# hub.net
KiCad netlist of a schematic drawn in EAGLE
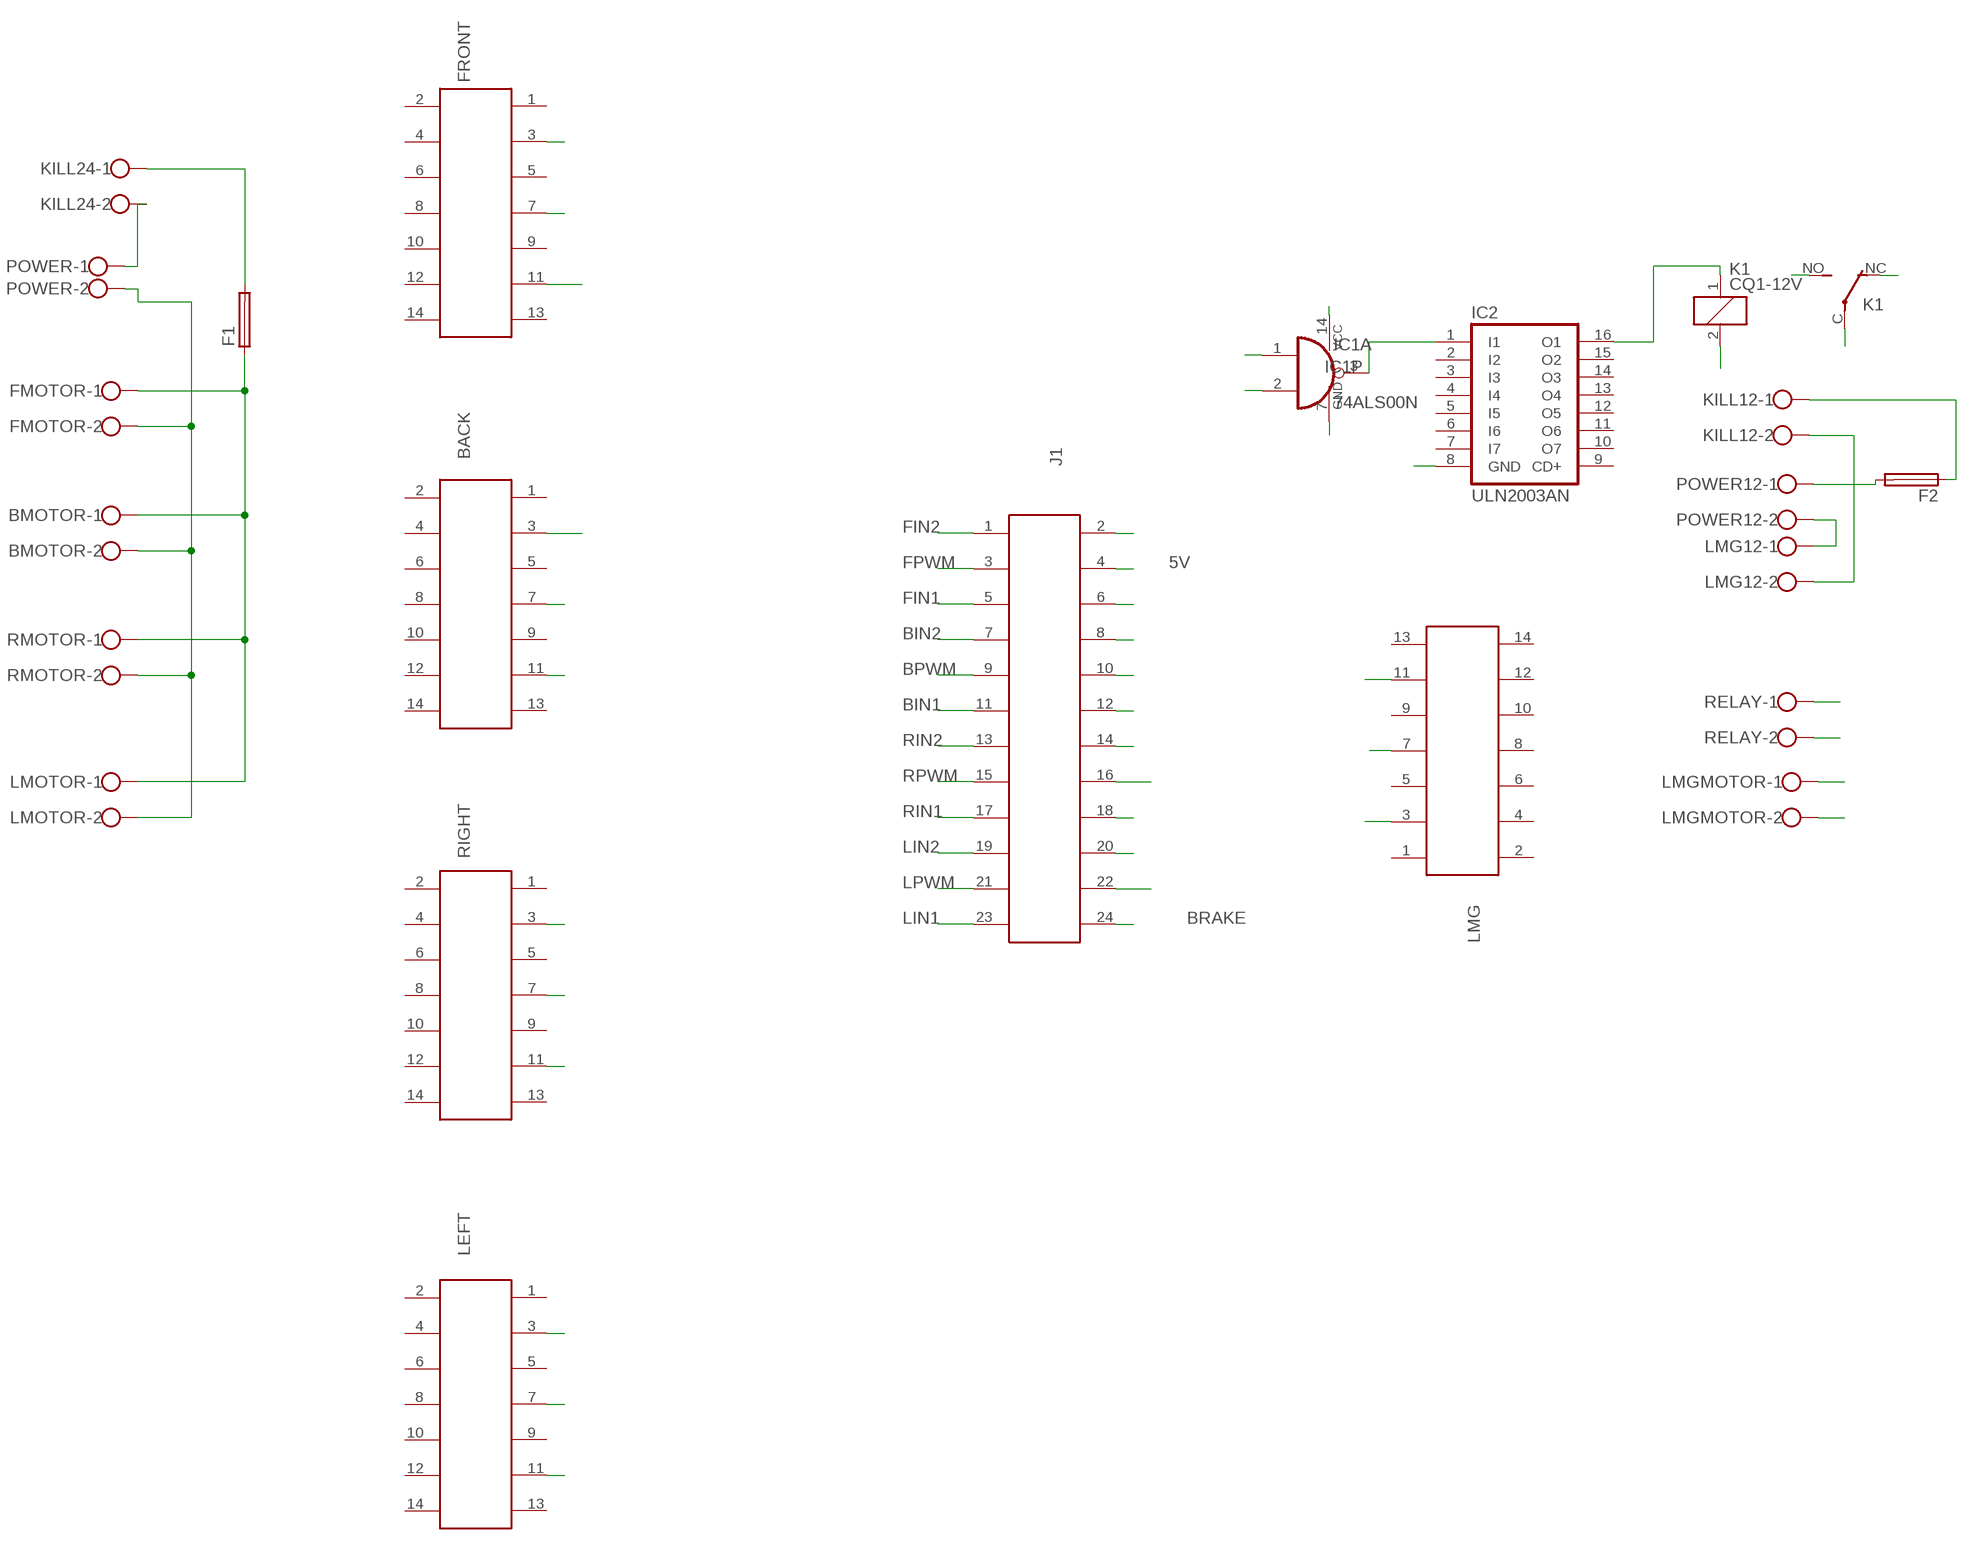
[diagram p0: schematic, sheet 1]

(export (version "E")
  (design (tool "Eeschema 10.0.6"))
  (components
    (comp (ref "BACK")
      (value "612014235121")
      (footprint "eagle-import:612014235121")
      (libsource (lib "eagle-import") (part "612014235121"))
    )
    (comp (ref "BMOTOR")
      (value "W237-102")
      (footprint "eagle-import:W237-102")
      (fields (field (name "MPN") "237-102"))
      (libsource (lib "eagle-import") (part "W237-102"))
    )
    (comp (ref "F1")
      (value "GSH15")
      (footprint "eagle-import:GSH15")
      (fields (field (name "MPN") "64900001039"))
      (libsource (lib "eagle-import") (part "GSH15"))
    )
    (comp (ref "F2")
      (value "GSH15")
      (footprint "eagle-import:GSH15")
      (fields (field (name "MPN") "64900001039"))
      (libsource (lib "eagle-import") (part "GSH15"))
    )
    (comp (ref "FMOTOR")
      (value "W237-102")
      (footprint "eagle-import:W237-102")
      (fields (field (name "MPN") "237-102"))
      (libsource (lib "eagle-import") (part "W237-102"))
    )
    (comp (ref "FRONT")
      (value "612014235121")
      (footprint "eagle-import:612014235121")
      (libsource (lib "eagle-import") (part "612014235121"))
    )
    (comp (ref "IC1")
      (value "74ALS00N")
      (footprint "eagle-import:DIL14")
      (libsource (lib "eagle-import") (part "7400NALS"))
    )
    (comp (ref "IC2")
      (value "ULN2003AN")
      (footprint "eagle-import:DIL16")
      (libsource (lib "eagle-import") (part "ULN2003AN"))
    )
    (comp (ref "J1")
      (value "61202421621")
      (footprint "eagle-import:61202421621")
      (libsource (lib "eagle-import") (part "61202421621"))
    )
    (comp (ref "K1")
      (value "CQ1-12V")
      (footprint "eagle-import:CQ1")
      (libsource (lib "eagle-import") (part "CQ1-12V"))
    )
    (comp (ref "KILL12")
      (value "W237-102")
      (footprint "eagle-import:W237-102")
      (fields (field (name "MPN") "237-102"))
      (libsource (lib "eagle-import") (part "W237-102"))
    )
    (comp (ref "KILL24")
      (value "W237-102")
      (footprint "eagle-import:W237-102")
      (fields (field (name "MPN") "237-102"))
      (libsource (lib "eagle-import") (part "W237-102"))
    )
    (comp (ref "LEFT")
      (value "612014235121")
      (footprint "eagle-import:612014235121")
      (libsource (lib "eagle-import") (part "612014235121"))
    )
    (comp (ref "LMG")
      (value "612014235121")
      (footprint "eagle-import:612014235121")
      (libsource (lib "eagle-import") (part "612014235121"))
    )
    (comp (ref "LMG12")
      (value "W237-102")
      (footprint "eagle-import:W237-102")
      (fields (field (name "MPN") "237-102"))
      (libsource (lib "eagle-import") (part "W237-102"))
    )
    (comp (ref "LMGMOTOR")
      (value "W237-102")
      (footprint "eagle-import:W237-102")
      (fields (field (name "MPN") "237-102"))
      (libsource (lib "eagle-import") (part "W237-102"))
    )
    (comp (ref "LMOTOR")
      (value "W237-102")
      (footprint "eagle-import:W237-102")
      (fields (field (name "MPN") "237-102"))
      (libsource (lib "eagle-import") (part "W237-102"))
    )
    (comp (ref "POWER")
      (value "W237-102")
      (footprint "eagle-import:W237-102")
      (fields (field (name "MPN") "237-102"))
      (libsource (lib "eagle-import") (part "W237-102"))
    )
    (comp (ref "POWER12")
      (value "W237-102")
      (footprint "eagle-import:W237-102")
      (fields (field (name "MPN") "237-102"))
      (libsource (lib "eagle-import") (part "W237-102"))
    )
    (comp (ref "RELAY")
      (value "W237-102")
      (footprint "eagle-import:W237-102")
      (fields (field (name "MPN") "237-102"))
      (libsource (lib "eagle-import") (part "W237-102"))
    )
    (comp (ref "RIGHT")
      (value "612014235121")
      (footprint "eagle-import:612014235121")
      (libsource (lib "eagle-import") (part "612014235121"))
    )
    (comp (ref "RMOTOR")
      (value "W237-102")
      (footprint "eagle-import:W237-102")
      (fields (field (name "MPN") "237-102"))
      (libsource (lib "eagle-import") (part "W237-102"))
    )
  )
  (nets
    (net (code "1") (name "/5V") (class "Default")
      (node (ref "IC1") (pin "1") (pinfunction "I0_1") (pintype "input"))
      (node (ref "IC1") (pin "14") (pinfunction "VCC_14") (pintype "power_in"))
      (node (ref "J1") (pin "4") (pinfunction "4_4") (pintype "passive"))
      (node (ref "K1") (pin "2") (pinfunction "2_2") (pintype "passive"))
    )
    (net (code "2") (name "/BIN1") (class "Default")
      (node (ref "BACK") (pin "3") (pinfunction "3_3") (pintype "passive"))
      (node (ref "J1") (pin "11") (pinfunction "11_11") (pintype "passive"))
    )
    (net (code "3") (name "/BIN2") (class "Default")
      (node (ref "BACK") (pin "11") (pinfunction "11_11") (pintype "passive"))
      (node (ref "J1") (pin "7") (pinfunction "7_7") (pintype "passive"))
    )
    (net (code "4") (name "/BPWM") (class "Default")
      (node (ref "BACK") (pin "7") (pinfunction "7_7") (pintype "passive"))
      (node (ref "J1") (pin "9") (pinfunction "9_9") (pintype "passive"))
    )
    (net (code "5") (name "/BRAKE") (class "Default")
      (node (ref "IC1") (pin "2") (pinfunction "I1_2") (pintype "input"))
      (node (ref "J1") (pin "24") (pinfunction "24_24") (pintype "passive"))
    )
    (net (code "6") (name "/COM") (class "Default")
      (node (ref "K1") (pin "C") (pinfunction "P_C") (pintype "passive"))
      (node (ref "LMGMOTOR") (pin "2") (pinfunction "KL_2") (pintype "passive"))
      (node (ref "RELAY") (pin "2") (pinfunction "KL_2") (pintype "passive"))
    )
    (net (code "7") (name "/FIN1") (class "Default")
      (node (ref "FRONT") (pin "3") (pinfunction "3_3") (pintype "passive"))
      (node (ref "J1") (pin "5") (pinfunction "5_5") (pintype "passive"))
    )
    (net (code "8") (name "/FIN2") (class "Default")
      (node (ref "FRONT") (pin "11") (pinfunction "11_11") (pintype "passive"))
      (node (ref "J1") (pin "1") (pinfunction "1_1") (pintype "passive"))
    )
    (net (code "9") (name "/FPWM") (class "Default")
      (node (ref "FRONT") (pin "7") (pinfunction "7_7") (pintype "passive"))
      (node (ref "J1") (pin "3") (pinfunction "3_3") (pintype "passive"))
    )
    (net (code "10") (name "/GND") (class "Default")
      (node (ref "BMOTOR") (pin "2") (pinfunction "KL_2") (pintype "passive"))
      (node (ref "FMOTOR") (pin "2") (pinfunction "KL_2") (pintype "passive"))
      (node (ref "IC1") (pin "7") (pinfunction "GND_7") (pintype "power_in"))
      (node (ref "IC2") (pin "8") (pinfunction "GND_8") (pintype "power_in"))
      (node (ref "LMOTOR") (pin "2") (pinfunction "KL_2") (pintype "passive"))
      (node (ref "POWER") (pin "2") (pinfunction "KL_2") (pintype "passive"))
      (node (ref "RMOTOR") (pin "2") (pinfunction "KL_2") (pintype "passive"))
    )
    (net (code "11") (name "/LIN1") (class "Default")
      (node (ref "J1") (pin "23") (pinfunction "23_23") (pintype "passive"))
      (node (ref "LEFT") (pin "3") (pinfunction "3_3") (pintype "passive"))
    )
    (net (code "12") (name "/LIN2") (class "Default")
      (node (ref "J1") (pin "19") (pinfunction "19_19") (pintype "passive"))
      (node (ref "LEFT") (pin "11") (pinfunction "11_11") (pintype "passive"))
    )
    (net (code "13") (name "/LMG1") (class "Default")
      (node (ref "J1") (pin "14") (pinfunction "14_14") (pintype "passive"))
      (node (ref "LMG") (pin "3") (pinfunction "3_3") (pintype "passive"))
    )
    (net (code "14") (name "/LMG2") (class "Default")
      (node (ref "J1") (pin "18") (pinfunction "18_18") (pintype "passive"))
      (node (ref "LMG") (pin "11") (pinfunction "11_11") (pintype "passive"))
    )
    (net (code "15") (name "/LMGPWM") (class "Default")
      (node (ref "J1") (pin "16") (pinfunction "16_16") (pintype "passive"))
      (node (ref "LMG") (pin "7") (pinfunction "7_7") (pintype "passive"))
    )
    (net (code "16") (name "/LPWM") (class "Default")
      (node (ref "J1") (pin "21") (pinfunction "21_21") (pintype "passive"))
      (node (ref "LEFT") (pin "7") (pinfunction "7_7") (pintype "passive"))
    )
    (net (code "17") (name "/NO") (class "Default")
      (node (ref "K1") (pin "NO") (pinfunction "S_NO") (pintype "passive"))
      (node (ref "LMGMOTOR") (pin "1") (pinfunction "KL_1") (pintype "passive"))
      (node (ref "RELAY") (pin "1") (pinfunction "KL_1") (pintype "passive"))
    )
    (net (code "18") (name "/RIN1") (class "Default")
      (node (ref "J1") (pin "17") (pinfunction "17_17") (pintype "passive"))
      (node (ref "RIGHT") (pin "3") (pinfunction "3_3") (pintype "passive"))
    )
    (net (code "19") (name "/RIN2") (class "Default")
      (node (ref "J1") (pin "13") (pinfunction "13_13") (pintype "passive"))
      (node (ref "RIGHT") (pin "11") (pinfunction "11_11") (pintype "passive"))
    )
    (net (code "20") (name "/RPWM") (class "Default")
      (node (ref "J1") (pin "15") (pinfunction "15_15") (pintype "passive"))
      (node (ref "RIGHT") (pin "7") (pinfunction "7_7") (pintype "passive"))
    )
    (net (code "21") (name "Net-(BMOTORA-KL)") (class "Default")
      (node (ref "BMOTOR") (pin "1") (pinfunction "KL_1") (pintype "passive"))
      (node (ref "F1") (pin "1") (pinfunction "1_1") (pintype "passive"))
      (node (ref "FMOTOR") (pin "1") (pinfunction "KL_1") (pintype "passive"))
      (node (ref "LMOTOR") (pin "1") (pinfunction "KL_1") (pintype "passive"))
      (node (ref "RMOTOR") (pin "1") (pinfunction "KL_1") (pintype "passive"))
    )
    (net (code "22") (name "Net-(IC1A-O)") (class "Default")
      (node (ref "IC1") (pin "3") (pinfunction "O_3") (pintype "output"))
      (node (ref "IC2") (pin "1") (pinfunction "I1_1") (pintype "input"))
    )
    (net (code "23") (name "Net-(IC2-O1)") (class "Default")
      (node (ref "IC2") (pin "16") (pinfunction "O1_16") (pintype "open_collector"))
      (node (ref "K1") (pin "1") (pinfunction "1_1") (pintype "passive"))
    )
    (net (code "24") (name "Net-(KILL12A-KL)") (class "Default")
      (node (ref "F2") (pin "1") (pinfunction "1_1") (pintype "passive"))
      (node (ref "KILL12") (pin "1") (pinfunction "KL_1") (pintype "passive"))
    )
    (net (code "25") (name "Net-(KILL12B-KL)") (class "Default")
      (node (ref "KILL12") (pin "2") (pinfunction "KL_2") (pintype "passive"))
      (node (ref "LMG12") (pin "2") (pinfunction "KL_2") (pintype "passive"))
    )
    (net (code "26") (name "Net-(KILL24A-KL)") (class "Default")
      (node (ref "F1") (pin "2") (pinfunction "2_2") (pintype "passive"))
      (node (ref "KILL24") (pin "1") (pinfunction "KL_1") (pintype "passive"))
    )
    (net (code "27") (name "Net-(KILL24B-KL)") (class "Default")
      (node (ref "KILL24") (pin "2") (pinfunction "KL_2") (pintype "passive"))
      (node (ref "POWER") (pin "1") (pinfunction "KL_1") (pintype "passive"))
    )
    (net (code "28") (name "Net-(LMG12A-KL)") (class "Default")
      (node (ref "LMG12") (pin "1") (pinfunction "KL_1") (pintype "passive"))
      (node (ref "POWER12") (pin "2") (pinfunction "KL_2") (pintype "passive"))
    )
    (net (code "29") (name "Net-(POWER12A-KL)") (class "Default")
      (node (ref "F2") (pin "2") (pinfunction "2_2") (pintype "passive"))
      (node (ref "POWER12") (pin "1") (pinfunction "KL_1") (pintype "passive"))
    )
    (net (code "30") (name "unconnected-(BACK-Pad1)") (class "Default")
      (node (ref "BACK") (pin "1") (pinfunction "1_1") (pintype "passive"))
    )
    (net (code "31") (name "unconnected-(BACK-Pad2)") (class "Default")
      (node (ref "BACK") (pin "2") (pinfunction "2_2") (pintype "passive"))
    )
    (net (code "32") (name "unconnected-(BACK-Pad4)") (class "Default")
      (node (ref "BACK") (pin "4") (pinfunction "4_4") (pintype "passive"))
    )
    (net (code "33") (name "unconnected-(BACK-Pad5)") (class "Default")
      (node (ref "BACK") (pin "5") (pinfunction "5_5") (pintype "passive"))
    )
    (net (code "34") (name "unconnected-(BACK-Pad6)") (class "Default")
      (node (ref "BACK") (pin "6") (pinfunction "6_6") (pintype "passive"))
    )
    (net (code "35") (name "unconnected-(BACK-Pad8)") (class "Default")
      (node (ref "BACK") (pin "8") (pinfunction "8_8") (pintype "passive"))
    )
    (net (code "36") (name "unconnected-(BACK-Pad9)") (class "Default")
      (node (ref "BACK") (pin "9") (pinfunction "9_9") (pintype "passive"))
    )
    (net (code "37") (name "unconnected-(BACK-Pad10)") (class "Default")
      (node (ref "BACK") (pin "10") (pinfunction "10_10") (pintype "passive"))
    )
    (net (code "38") (name "unconnected-(BACK-Pad12)") (class "Default")
      (node (ref "BACK") (pin "12") (pinfunction "12_12") (pintype "passive"))
    )
    (net (code "39") (name "unconnected-(BACK-Pad13)") (class "Default")
      (node (ref "BACK") (pin "13") (pinfunction "13_13") (pintype "passive"))
    )
    (net (code "40") (name "unconnected-(BACK-Pad14)") (class "Default")
      (node (ref "BACK") (pin "14") (pinfunction "14_14") (pintype "passive"))
    )
    (net (code "41") (name "unconnected-(FRONT-Pad1)") (class "Default")
      (node (ref "FRONT") (pin "1") (pinfunction "1_1") (pintype "passive"))
    )
    (net (code "42") (name "unconnected-(FRONT-Pad2)") (class "Default")
      (node (ref "FRONT") (pin "2") (pinfunction "2_2") (pintype "passive"))
    )
    (net (code "43") (name "unconnected-(FRONT-Pad4)") (class "Default")
      (node (ref "FRONT") (pin "4") (pinfunction "4_4") (pintype "passive"))
    )
    (net (code "44") (name "unconnected-(FRONT-Pad5)") (class "Default")
      (node (ref "FRONT") (pin "5") (pinfunction "5_5") (pintype "passive"))
    )
    (net (code "45") (name "unconnected-(FRONT-Pad6)") (class "Default")
      (node (ref "FRONT") (pin "6") (pinfunction "6_6") (pintype "passive"))
    )
    (net (code "46") (name "unconnected-(FRONT-Pad8)") (class "Default")
      (node (ref "FRONT") (pin "8") (pinfunction "8_8") (pintype "passive"))
    )
    (net (code "47") (name "unconnected-(FRONT-Pad9)") (class "Default")
      (node (ref "FRONT") (pin "9") (pinfunction "9_9") (pintype "passive"))
    )
    (net (code "48") (name "unconnected-(FRONT-Pad10)") (class "Default")
      (node (ref "FRONT") (pin "10") (pinfunction "10_10") (pintype "passive"))
    )
    (net (code "49") (name "unconnected-(FRONT-Pad12)") (class "Default")
      (node (ref "FRONT") (pin "12") (pinfunction "12_12") (pintype "passive"))
    )
    (net (code "50") (name "unconnected-(FRONT-Pad13)") (class "Default")
      (node (ref "FRONT") (pin "13") (pinfunction "13_13") (pintype "passive"))
    )
    (net (code "51") (name "unconnected-(FRONT-Pad14)") (class "Default")
      (node (ref "FRONT") (pin "14") (pinfunction "14_14") (pintype "passive"))
    )
    (net (code "52") (name "unconnected-(IC2-CD+-Pad9)") (class "Default")
      (node (ref "IC2") (pin "9") (pinfunction "CD+_9") (pintype "passive"))
    )
    (net (code "53") (name "unconnected-(IC2-I2-Pad2)") (class "Default")
      (node (ref "IC2") (pin "2") (pinfunction "I2_2") (pintype "input"))
    )
    (net (code "54") (name "unconnected-(IC2-I3-Pad3)") (class "Default")
      (node (ref "IC2") (pin "3") (pinfunction "I3_3") (pintype "input"))
    )
    (net (code "55") (name "unconnected-(IC2-I4-Pad4)") (class "Default")
      (node (ref "IC2") (pin "4") (pinfunction "I4_4") (pintype "input"))
    )
    (net (code "56") (name "unconnected-(IC2-I5-Pad5)") (class "Default")
      (node (ref "IC2") (pin "5") (pinfunction "I5_5") (pintype "input"))
    )
    (net (code "57") (name "unconnected-(IC2-I6-Pad6)") (class "Default")
      (node (ref "IC2") (pin "6") (pinfunction "I6_6") (pintype "input"))
    )
    (net (code "58") (name "unconnected-(IC2-I7-Pad7)") (class "Default")
      (node (ref "IC2") (pin "7") (pinfunction "I7_7") (pintype "input"))
    )
    (net (code "59") (name "unconnected-(IC2-O2-Pad15)") (class "Default")
      (node (ref "IC2") (pin "15") (pinfunction "O2_15") (pintype "open_collector"))
    )
    (net (code "60") (name "unconnected-(IC2-O3-Pad14)") (class "Default")
      (node (ref "IC2") (pin "14") (pinfunction "O3_14") (pintype "open_collector"))
    )
    (net (code "61") (name "unconnected-(IC2-O4-Pad13)") (class "Default")
      (node (ref "IC2") (pin "13") (pinfunction "O4_13") (pintype "open_collector"))
    )
    (net (code "62") (name "unconnected-(IC2-O5-Pad12)") (class "Default")
      (node (ref "IC2") (pin "12") (pinfunction "O5_12") (pintype "open_collector"))
    )
    (net (code "63") (name "unconnected-(IC2-O6-Pad11)") (class "Default")
      (node (ref "IC2") (pin "11") (pinfunction "O6_11") (pintype "open_collector"))
    )
    (net (code "64") (name "unconnected-(IC2-O7-Pad10)") (class "Default")
      (node (ref "IC2") (pin "10") (pinfunction "O7_10") (pintype "open_collector"))
    )
    (net (code "65") (name "unconnected-(J1-Pad2)") (class "Default")
      (node (ref "J1") (pin "2") (pinfunction "2_2") (pintype "passive"))
    )
    (net (code "66") (name "unconnected-(J1-Pad6)") (class "Default")
      (node (ref "J1") (pin "6") (pinfunction "6_6") (pintype "passive"))
    )
    (net (code "67") (name "unconnected-(J1-Pad8)") (class "Default")
      (node (ref "J1") (pin "8") (pinfunction "8_8") (pintype "passive"))
    )
    (net (code "68") (name "unconnected-(J1-Pad10)") (class "Default")
      (node (ref "J1") (pin "10") (pinfunction "10_10") (pintype "passive"))
    )
    (net (code "69") (name "unconnected-(J1-Pad12)") (class "Default")
      (node (ref "J1") (pin "12") (pinfunction "12_12") (pintype "passive"))
    )
    (net (code "70") (name "unconnected-(J1-Pad20)") (class "Default")
      (node (ref "J1") (pin "20") (pinfunction "20_20") (pintype "passive"))
    )
    (net (code "71") (name "unconnected-(J1-Pad22)") (class "Default")
      (node (ref "J1") (pin "22") (pinfunction "22_22") (pintype "passive"))
    )
    (net (code "72") (name "unconnected-(K1B-O-PadNC)") (class "Default")
      (node (ref "K1") (pin "NC") (pinfunction "O_NC") (pintype "passive"))
    )
    (net (code "73") (name "unconnected-(LEFT-Pad1)") (class "Default")
      (node (ref "LEFT") (pin "1") (pinfunction "1_1") (pintype "passive"))
    )
    (net (code "74") (name "unconnected-(LEFT-Pad2)") (class "Default")
      (node (ref "LEFT") (pin "2") (pinfunction "2_2") (pintype "passive"))
    )
    (net (code "75") (name "unconnected-(LEFT-Pad4)") (class "Default")
      (node (ref "LEFT") (pin "4") (pinfunction "4_4") (pintype "passive"))
    )
    (net (code "76") (name "unconnected-(LEFT-Pad5)") (class "Default")
      (node (ref "LEFT") (pin "5") (pinfunction "5_5") (pintype "passive"))
    )
    (net (code "77") (name "unconnected-(LEFT-Pad6)") (class "Default")
      (node (ref "LEFT") (pin "6") (pinfunction "6_6") (pintype "passive"))
    )
    (net (code "78") (name "unconnected-(LEFT-Pad8)") (class "Default")
      (node (ref "LEFT") (pin "8") (pinfunction "8_8") (pintype "passive"))
    )
    (net (code "79") (name "unconnected-(LEFT-Pad9)") (class "Default")
      (node (ref "LEFT") (pin "9") (pinfunction "9_9") (pintype "passive"))
    )
    (net (code "80") (name "unconnected-(LEFT-Pad10)") (class "Default")
      (node (ref "LEFT") (pin "10") (pinfunction "10_10") (pintype "passive"))
    )
    (net (code "81") (name "unconnected-(LEFT-Pad12)") (class "Default")
      (node (ref "LEFT") (pin "12") (pinfunction "12_12") (pintype "passive"))
    )
    (net (code "82") (name "unconnected-(LEFT-Pad13)") (class "Default")
      (node (ref "LEFT") (pin "13") (pinfunction "13_13") (pintype "passive"))
    )
    (net (code "83") (name "unconnected-(LEFT-Pad14)") (class "Default")
      (node (ref "LEFT") (pin "14") (pinfunction "14_14") (pintype "passive"))
    )
    (net (code "84") (name "unconnected-(LMG-Pad1)") (class "Default")
      (node (ref "LMG") (pin "1") (pinfunction "1_1") (pintype "passive"))
    )
    (net (code "85") (name "unconnected-(LMG-Pad2)") (class "Default")
      (node (ref "LMG") (pin "2") (pinfunction "2_2") (pintype "passive"))
    )
    (net (code "86") (name "unconnected-(LMG-Pad4)") (class "Default")
      (node (ref "LMG") (pin "4") (pinfunction "4_4") (pintype "passive"))
    )
    (net (code "87") (name "unconnected-(LMG-Pad5)") (class "Default")
      (node (ref "LMG") (pin "5") (pinfunction "5_5") (pintype "passive"))
    )
    (net (code "88") (name "unconnected-(LMG-Pad6)") (class "Default")
      (node (ref "LMG") (pin "6") (pinfunction "6_6") (pintype "passive"))
    )
    (net (code "89") (name "unconnected-(LMG-Pad8)") (class "Default")
      (node (ref "LMG") (pin "8") (pinfunction "8_8") (pintype "passive"))
    )
    (net (code "90") (name "unconnected-(LMG-Pad9)") (class "Default")
      (node (ref "LMG") (pin "9") (pinfunction "9_9") (pintype "passive"))
    )
    (net (code "91") (name "unconnected-(LMG-Pad10)") (class "Default")
      (node (ref "LMG") (pin "10") (pinfunction "10_10") (pintype "passive"))
    )
    (net (code "92") (name "unconnected-(LMG-Pad12)") (class "Default")
      (node (ref "LMG") (pin "12") (pinfunction "12_12") (pintype "passive"))
    )
    (net (code "93") (name "unconnected-(LMG-Pad13)") (class "Default")
      (node (ref "LMG") (pin "13") (pinfunction "13_13") (pintype "passive"))
    )
    (net (code "94") (name "unconnected-(LMG-Pad14)") (class "Default")
      (node (ref "LMG") (pin "14") (pinfunction "14_14") (pintype "passive"))
    )
    (net (code "95") (name "unconnected-(RIGHT-Pad1)") (class "Default")
      (node (ref "RIGHT") (pin "1") (pinfunction "1_1") (pintype "passive"))
    )
    (net (code "96") (name "unconnected-(RIGHT-Pad2)") (class "Default")
      (node (ref "RIGHT") (pin "2") (pinfunction "2_2") (pintype "passive"))
    )
    (net (code "97") (name "unconnected-(RIGHT-Pad4)") (class "Default")
      (node (ref "RIGHT") (pin "4") (pinfunction "4_4") (pintype "passive"))
    )
    (net (code "98") (name "unconnected-(RIGHT-Pad5)") (class "Default")
      (node (ref "RIGHT") (pin "5") (pinfunction "5_5") (pintype "passive"))
    )
    (net (code "99") (name "unconnected-(RIGHT-Pad6)") (class "Default")
      (node (ref "RIGHT") (pin "6") (pinfunction "6_6") (pintype "passive"))
    )
    (net (code "100") (name "unconnected-(RIGHT-Pad8)") (class "Default")
      (node (ref "RIGHT") (pin "8") (pinfunction "8_8") (pintype "passive"))
    )
    (net (code "101") (name "unconnected-(RIGHT-Pad9)") (class "Default")
      (node (ref "RIGHT") (pin "9") (pinfunction "9_9") (pintype "passive"))
    )
    (net (code "102") (name "unconnected-(RIGHT-Pad10)") (class "Default")
      (node (ref "RIGHT") (pin "10") (pinfunction "10_10") (pintype "passive"))
    )
    (net (code "103") (name "unconnected-(RIGHT-Pad12)") (class "Default")
      (node (ref "RIGHT") (pin "12") (pinfunction "12_12") (pintype "passive"))
    )
    (net (code "104") (name "unconnected-(RIGHT-Pad13)") (class "Default")
      (node (ref "RIGHT") (pin "13") (pinfunction "13_13") (pintype "passive"))
    )
    (net (code "105") (name "unconnected-(RIGHT-Pad14)") (class "Default")
      (node (ref "RIGHT") (pin "14") (pinfunction "14_14") (pintype "passive"))
    )
  )
)
